# schematics.net
KiCad netlist of a schematic drawn in EasyEDA
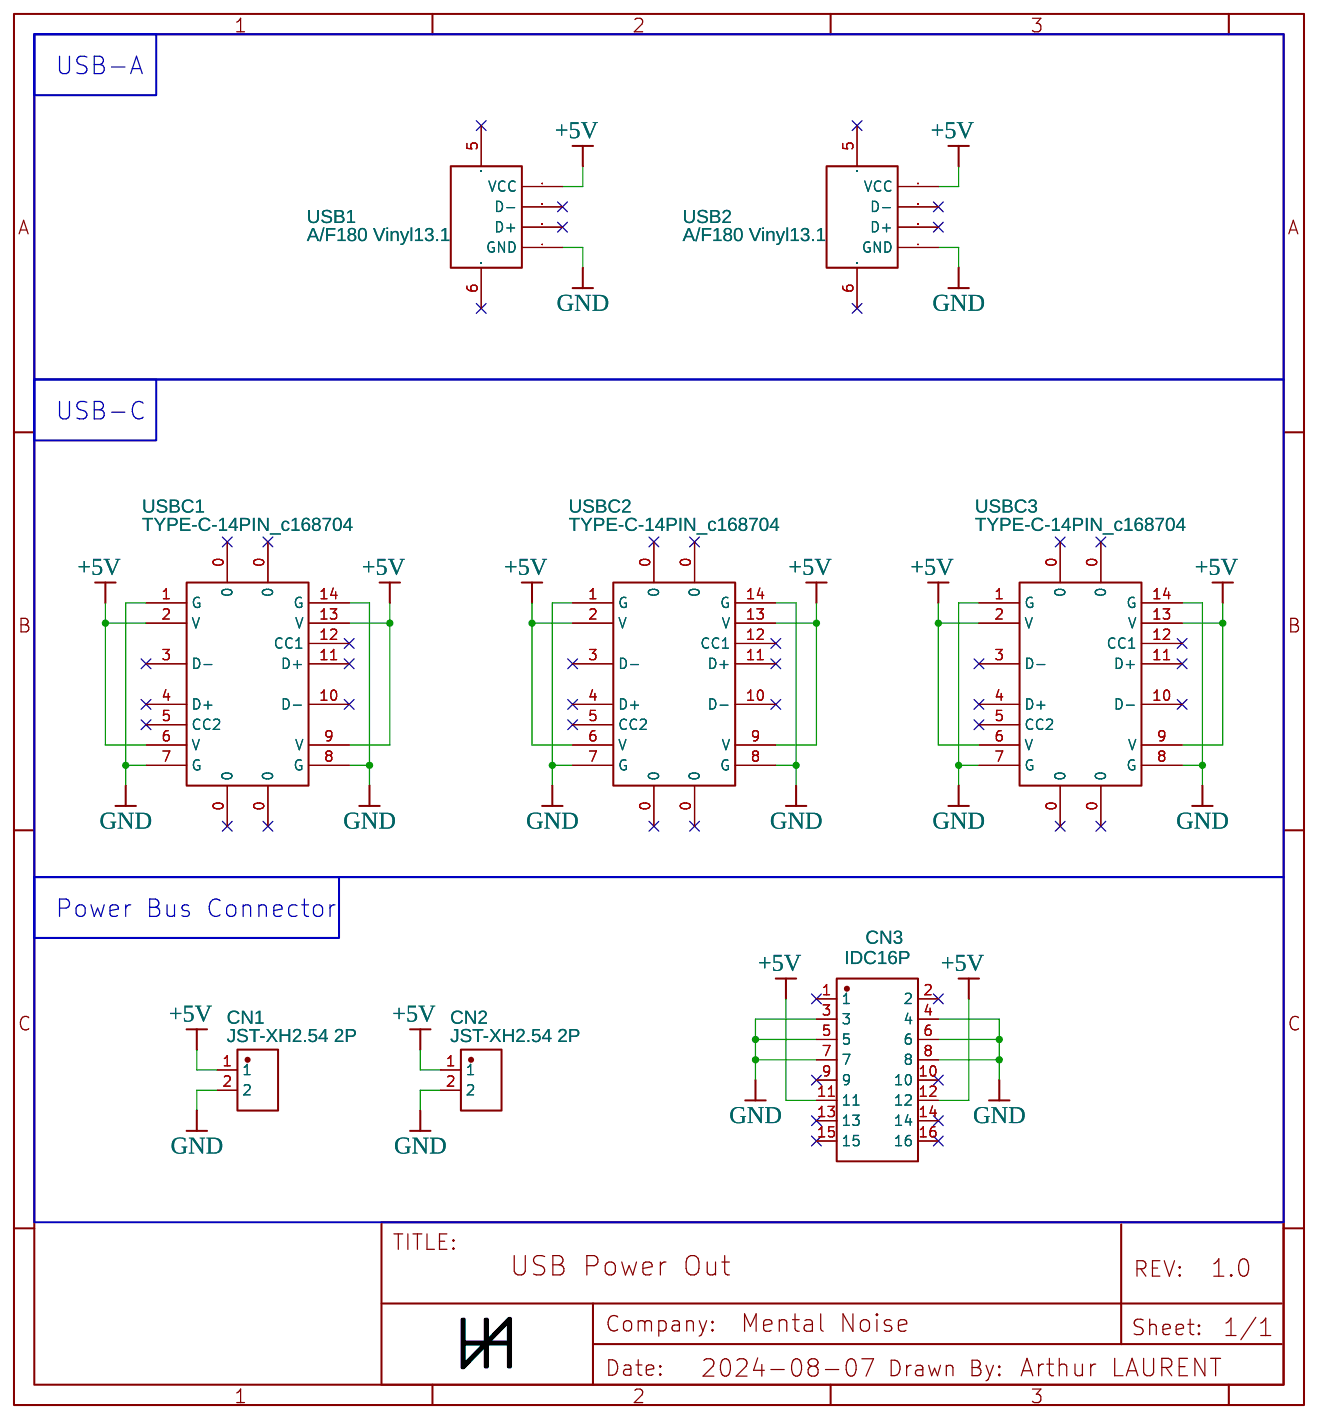
[diagram p0: schematic sheet]

(export (version "E")
  (design (tool "Eeschema 10.0.6"))
  (components
    (comp (ref "CN1") (value "JST-XH2.54 2P") (libsource (lib "") (part "JST-XH2.54 2P")))
    (comp (ref "CN2") (value "JST-XH2.54 2P") (libsource (lib "") (part "JST-XH2.54 2P")))
    (comp (ref "CN3")
      (value "IDC16P")
      (fields
        (field (name "Manufacturer Part") "MZ254R-22-16-10")
        (field (name "Manufacturer") "DEALON(德艺隆)")
      )
      (libsource (lib "") (part "MZ254R-22-16-10"))
    )
    (comp (ref "USB1")
      (value "A/F180 Vinyl13.1")
      (fields (field (name "Manufacturer Part") "916-151A1022Y10200") (field (name "Manufacturer") "精拓金"))
      (libsource (lib "") (part "A/F180 Vinyl13.1"))
    )
    (comp (ref "USB2")
      (value "A/F180 Vinyl13.1")
      (fields (field (name "Manufacturer Part") "916-151A1022Y10200") (field (name "Manufacturer") "精拓金"))
      (libsource (lib "") (part "A/F180 Vinyl13.1"))
    )
    (comp (ref "USBC1")
      (value "TYPE-C-14PIN_c168704")
      (fields (field (name "Manufacturer") "LCSC"))
      (libsource (lib "") (part "TYPE-C-14PIN_c168704"))
    )
    (comp (ref "USBC2")
      (value "TYPE-C-14PIN_c168704")
      (fields (field (name "Manufacturer") "LCSC"))
      (libsource (lib "") (part "TYPE-C-14PIN_c168704"))
    )
    (comp (ref "USBC3")
      (value "TYPE-C-14PIN_c168704")
      (fields (field (name "Manufacturer") "LCSC"))
      (libsource (lib "") (part "TYPE-C-14PIN_c168704"))
    )
  )
  (nets
    (net (code "1") (name "+5V") (class "Default")
      (node (ref "CN1") (pin "1") (pinfunction "1_1") (pintype "unspecified"))
      (node (ref "CN2") (pin "1") (pinfunction "1_1") (pintype "unspecified"))
      (node (ref "CN3") (pin "11") (pinfunction "11_11") (pintype "unspecified"))
      (node (ref "CN3") (pin "12") (pinfunction "12_12") (pintype "unspecified"))
      (node (ref "USB1") (pin "1") (pinfunction "VCC_1") (pintype "input"))
      (node (ref "USB2") (pin "1") (pinfunction "VCC_1") (pintype "input"))
      (node (ref "USBC1") (pin "13") (pinfunction "V_13") (pintype "unspecified"))
      (node (ref "USBC1") (pin "2") (pinfunction "V_2") (pintype "unspecified"))
      (node (ref "USBC1") (pin "6") (pinfunction "V_6") (pintype "unspecified"))
      (node (ref "USBC1") (pin "9") (pinfunction "V_9") (pintype "unspecified"))
      (node (ref "USBC2") (pin "13") (pinfunction "V_13") (pintype "unspecified"))
      (node (ref "USBC2") (pin "2") (pinfunction "V_2") (pintype "unspecified"))
      (node (ref "USBC2") (pin "6") (pinfunction "V_6") (pintype "unspecified"))
      (node (ref "USBC2") (pin "9") (pinfunction "V_9") (pintype "unspecified"))
      (node (ref "USBC3") (pin "13") (pinfunction "V_13") (pintype "unspecified"))
      (node (ref "USBC3") (pin "2") (pinfunction "V_2") (pintype "unspecified"))
      (node (ref "USBC3") (pin "6") (pinfunction "V_6") (pintype "unspecified"))
      (node (ref "USBC3") (pin "9") (pinfunction "V_9") (pintype "unspecified"))
    )
    (net (code "2") (name "GND") (class "Default")
      (node (ref "CN1") (pin "2") (pinfunction "2_2") (pintype "unspecified"))
      (node (ref "CN2") (pin "2") (pinfunction "2_2") (pintype "unspecified"))
      (node (ref "CN3") (pin "3") (pinfunction "3_3") (pintype "unspecified"))
      (node (ref "CN3") (pin "4") (pinfunction "4_4") (pintype "unspecified"))
      (node (ref "CN3") (pin "5") (pinfunction "5_5") (pintype "unspecified"))
      (node (ref "CN3") (pin "6") (pinfunction "6_6") (pintype "unspecified"))
      (node (ref "CN3") (pin "7") (pinfunction "7_7") (pintype "unspecified"))
      (node (ref "CN3") (pin "8") (pinfunction "8_8") (pintype "unspecified"))
      (node (ref "USB1") (pin "4") (pinfunction "GND_4") (pintype "input"))
      (node (ref "USB2") (pin "4") (pinfunction "GND_4") (pintype "input"))
      (node (ref "USBC1") (pin "1") (pinfunction "G_1") (pintype "unspecified"))
      (node (ref "USBC1") (pin "14") (pinfunction "G_14") (pintype "unspecified"))
      (node (ref "USBC1") (pin "7") (pinfunction "G_7") (pintype "unspecified"))
      (node (ref "USBC1") (pin "8") (pinfunction "G_8") (pintype "unspecified"))
      (node (ref "USBC2") (pin "1") (pinfunction "G_1") (pintype "unspecified"))
      (node (ref "USBC2") (pin "14") (pinfunction "G_14") (pintype "unspecified"))
      (node (ref "USBC2") (pin "7") (pinfunction "G_7") (pintype "unspecified"))
      (node (ref "USBC2") (pin "8") (pinfunction "G_8") (pintype "unspecified"))
      (node (ref "USBC3") (pin "1") (pinfunction "G_1") (pintype "unspecified"))
      (node (ref "USBC3") (pin "14") (pinfunction "G_14") (pintype "unspecified"))
      (node (ref "USBC3") (pin "7") (pinfunction "G_7") (pintype "unspecified"))
      (node (ref "USBC3") (pin "8") (pinfunction "G_8") (pintype "unspecified"))
    )
    (net (code "3") (name "unconnected-(CN3-Pad1)") (class "Default")
      (node (ref "CN3") (pin "1") (pinfunction "1_1") (pintype "unspecified+no_connect"))
    )
    (net (code "4") (name "unconnected-(CN3-Pad2)") (class "Default")
      (node (ref "CN3") (pin "2") (pinfunction "2_2") (pintype "unspecified+no_connect"))
    )
    (net (code "5") (name "unconnected-(CN3-Pad9)") (class "Default")
      (node (ref "CN3") (pin "9") (pinfunction "9_9") (pintype "unspecified+no_connect"))
    )
    (net (code "6") (name "unconnected-(CN3-Pad10)") (class "Default")
      (node (ref "CN3") (pin "10") (pinfunction "10_10") (pintype "unspecified+no_connect"))
    )
    (net (code "7") (name "unconnected-(CN3-Pad13)") (class "Default")
      (node (ref "CN3") (pin "13") (pinfunction "13_13") (pintype "unspecified+no_connect"))
    )
    (net (code "8") (name "unconnected-(CN3-Pad14)") (class "Default")
      (node (ref "CN3") (pin "14") (pinfunction "14_14") (pintype "unspecified+no_connect"))
    )
    (net (code "9") (name "unconnected-(CN3-Pad15)") (class "Default")
      (node (ref "CN3") (pin "15") (pinfunction "15_15") (pintype "unspecified+no_connect"))
    )
    (net (code "10") (name "unconnected-(CN3-Pad16)") (class "Default")
      (node (ref "CN3") (pin "16") (pinfunction "16_16") (pintype "unspecified+no_connect"))
    )
    (net (code "11") (name "unconnected-(USB1-D+-Pad3)") (class "Default")
      (node (ref "USB1") (pin "3") (pinfunction "D+_3") (pintype "input+no_connect"))
    )
    (net (code "12") (name "unconnected-(USB1-D--Pad2)") (class "Default")
      (node (ref "USB1") (pin "2") (pinfunction "D-_2") (pintype "input+no_connect"))
    )
    (net (code "13") (name "unconnected-(USB1-Pad5)") (class "Default")
      (node (ref "USB1") (pin "5") (pinfunction "5_5") (pintype "unspecified+no_connect"))
    )
    (net (code "14") (name "unconnected-(USB1-Pad6)") (class "Default")
      (node (ref "USB1") (pin "6") (pinfunction "6_6") (pintype "unspecified+no_connect"))
    )
    (net (code "15") (name "unconnected-(USB2-D+-Pad3)") (class "Default")
      (node (ref "USB2") (pin "3") (pinfunction "D+_3") (pintype "input+no_connect"))
    )
    (net (code "16") (name "unconnected-(USB2-D--Pad2)") (class "Default")
      (node (ref "USB2") (pin "2") (pinfunction "D-_2") (pintype "input+no_connect"))
    )
    (net (code "17") (name "unconnected-(USB2-Pad5)") (class "Default")
      (node (ref "USB2") (pin "5") (pinfunction "5_5") (pintype "unspecified+no_connect"))
    )
    (net (code "18") (name "unconnected-(USB2-Pad6)") (class "Default")
      (node (ref "USB2") (pin "6") (pinfunction "6_6") (pintype "unspecified+no_connect"))
    )
    (net (code "19") (name "unconnected-(USBC1-CC1-Pad12)") (class "Default")
      (node (ref "USBC1") (pin "12") (pinfunction "CC1_12") (pintype "unspecified+no_connect"))
    )
    (net (code "20") (name "unconnected-(USBC1-CC2-Pad5)") (class "Default")
      (node (ref "USBC1") (pin "5") (pinfunction "CC2_5") (pintype "unspecified+no_connect"))
    )
    (net (code "21") (name "unconnected-(USBC1-D+-Pad4)") (class "Default")
      (node (ref "USBC1") (pin "4") (pinfunction "D+_4") (pintype "unspecified+no_connect"))
    )
    (net (code "22") (name "unconnected-(USBC1-D+-Pad11)") (class "Default")
      (node (ref "USBC1") (pin "11") (pinfunction "D+_11") (pintype "unspecified+no_connect"))
    )
    (net (code "23") (name "unconnected-(USBC1-D--Pad3)") (class "Default")
      (node (ref "USBC1") (pin "3") (pinfunction "D-_3") (pintype "unspecified+no_connect"))
    )
    (net (code "24") (name "unconnected-(USBC1-D--Pad10)") (class "Default")
      (node (ref "USBC1") (pin "10") (pinfunction "D-_10") (pintype "unspecified+no_connect"))
    )
    (net (code "25") (name "unconnected-(USBC1-Pad0)") (class "Default")
      (node (ref "USBC1") (pin "0") (pinfunction "0_0") (pintype "unspecified+no_connect"))
    )
    (net (code "26") (name "unconnected-(USBC1-Pad0)_1") (class "Default")
      (node (ref "USBC1") (pin "0") (pinfunction "0_0") (pintype "unspecified+no_connect"))
    )
    (net (code "27") (name "unconnected-(USBC1-Pad0)_2") (class "Default")
      (node (ref "USBC1") (pin "0") (pinfunction "0_0") (pintype "unspecified+no_connect"))
    )
    (net (code "28") (name "unconnected-(USBC1-Pad0)_3") (class "Default")
      (node (ref "USBC1") (pin "0") (pinfunction "0_0") (pintype "unspecified+no_connect"))
    )
    (net (code "29") (name "unconnected-(USBC2-CC1-Pad12)") (class "Default")
      (node (ref "USBC2") (pin "12") (pinfunction "CC1_12") (pintype "unspecified+no_connect"))
    )
    (net (code "30") (name "unconnected-(USBC2-CC2-Pad5)") (class "Default")
      (node (ref "USBC2") (pin "5") (pinfunction "CC2_5") (pintype "unspecified+no_connect"))
    )
    (net (code "31") (name "unconnected-(USBC2-D+-Pad4)") (class "Default")
      (node (ref "USBC2") (pin "4") (pinfunction "D+_4") (pintype "unspecified+no_connect"))
    )
    (net (code "32") (name "unconnected-(USBC2-D+-Pad11)") (class "Default")
      (node (ref "USBC2") (pin "11") (pinfunction "D+_11") (pintype "unspecified+no_connect"))
    )
    (net (code "33") (name "unconnected-(USBC2-D--Pad3)") (class "Default")
      (node (ref "USBC2") (pin "3") (pinfunction "D-_3") (pintype "unspecified+no_connect"))
    )
    (net (code "34") (name "unconnected-(USBC2-D--Pad10)") (class "Default")
      (node (ref "USBC2") (pin "10") (pinfunction "D-_10") (pintype "unspecified+no_connect"))
    )
    (net (code "35") (name "unconnected-(USBC2-Pad0)") (class "Default")
      (node (ref "USBC2") (pin "0") (pinfunction "0_0") (pintype "unspecified+no_connect"))
    )
    (net (code "36") (name "unconnected-(USBC2-Pad0)_1") (class "Default")
      (node (ref "USBC2") (pin "0") (pinfunction "0_0") (pintype "unspecified+no_connect"))
    )
    (net (code "37") (name "unconnected-(USBC2-Pad0)_2") (class "Default")
      (node (ref "USBC2") (pin "0") (pinfunction "0_0") (pintype "unspecified+no_connect"))
    )
    (net (code "38") (name "unconnected-(USBC2-Pad0)_3") (class "Default")
      (node (ref "USBC2") (pin "0") (pinfunction "0_0") (pintype "unspecified+no_connect"))
    )
    (net (code "39") (name "unconnected-(USBC3-CC1-Pad12)") (class "Default")
      (node (ref "USBC3") (pin "12") (pinfunction "CC1_12") (pintype "unspecified+no_connect"))
    )
    (net (code "40") (name "unconnected-(USBC3-CC2-Pad5)") (class "Default")
      (node (ref "USBC3") (pin "5") (pinfunction "CC2_5") (pintype "unspecified+no_connect"))
    )
    (net (code "41") (name "unconnected-(USBC3-D+-Pad4)") (class "Default")
      (node (ref "USBC3") (pin "4") (pinfunction "D+_4") (pintype "unspecified+no_connect"))
    )
    (net (code "42") (name "unconnected-(USBC3-D+-Pad11)") (class "Default")
      (node (ref "USBC3") (pin "11") (pinfunction "D+_11") (pintype "unspecified+no_connect"))
    )
    (net (code "43") (name "unconnected-(USBC3-D--Pad3)") (class "Default")
      (node (ref "USBC3") (pin "3") (pinfunction "D-_3") (pintype "unspecified+no_connect"))
    )
    (net (code "44") (name "unconnected-(USBC3-D--Pad10)") (class "Default")
      (node (ref "USBC3") (pin "10") (pinfunction "D-_10") (pintype "unspecified+no_connect"))
    )
    (net (code "45") (name "unconnected-(USBC3-Pad0)") (class "Default")
      (node (ref "USBC3") (pin "0") (pinfunction "0_0") (pintype "unspecified+no_connect"))
    )
    (net (code "46") (name "unconnected-(USBC3-Pad0)_1") (class "Default")
      (node (ref "USBC3") (pin "0") (pinfunction "0_0") (pintype "unspecified+no_connect"))
    )
    (net (code "47") (name "unconnected-(USBC3-Pad0)_2") (class "Default")
      (node (ref "USBC3") (pin "0") (pinfunction "0_0") (pintype "unspecified+no_connect"))
    )
    (net (code "48") (name "unconnected-(USBC3-Pad0)_3") (class "Default")
      (node (ref "USBC3") (pin "0") (pinfunction "0_0") (pintype "unspecified+no_connect"))
    )
  )
)
